# TurntableStrobe2.net
KiCad netlist of a schematic drawn in EAGLE
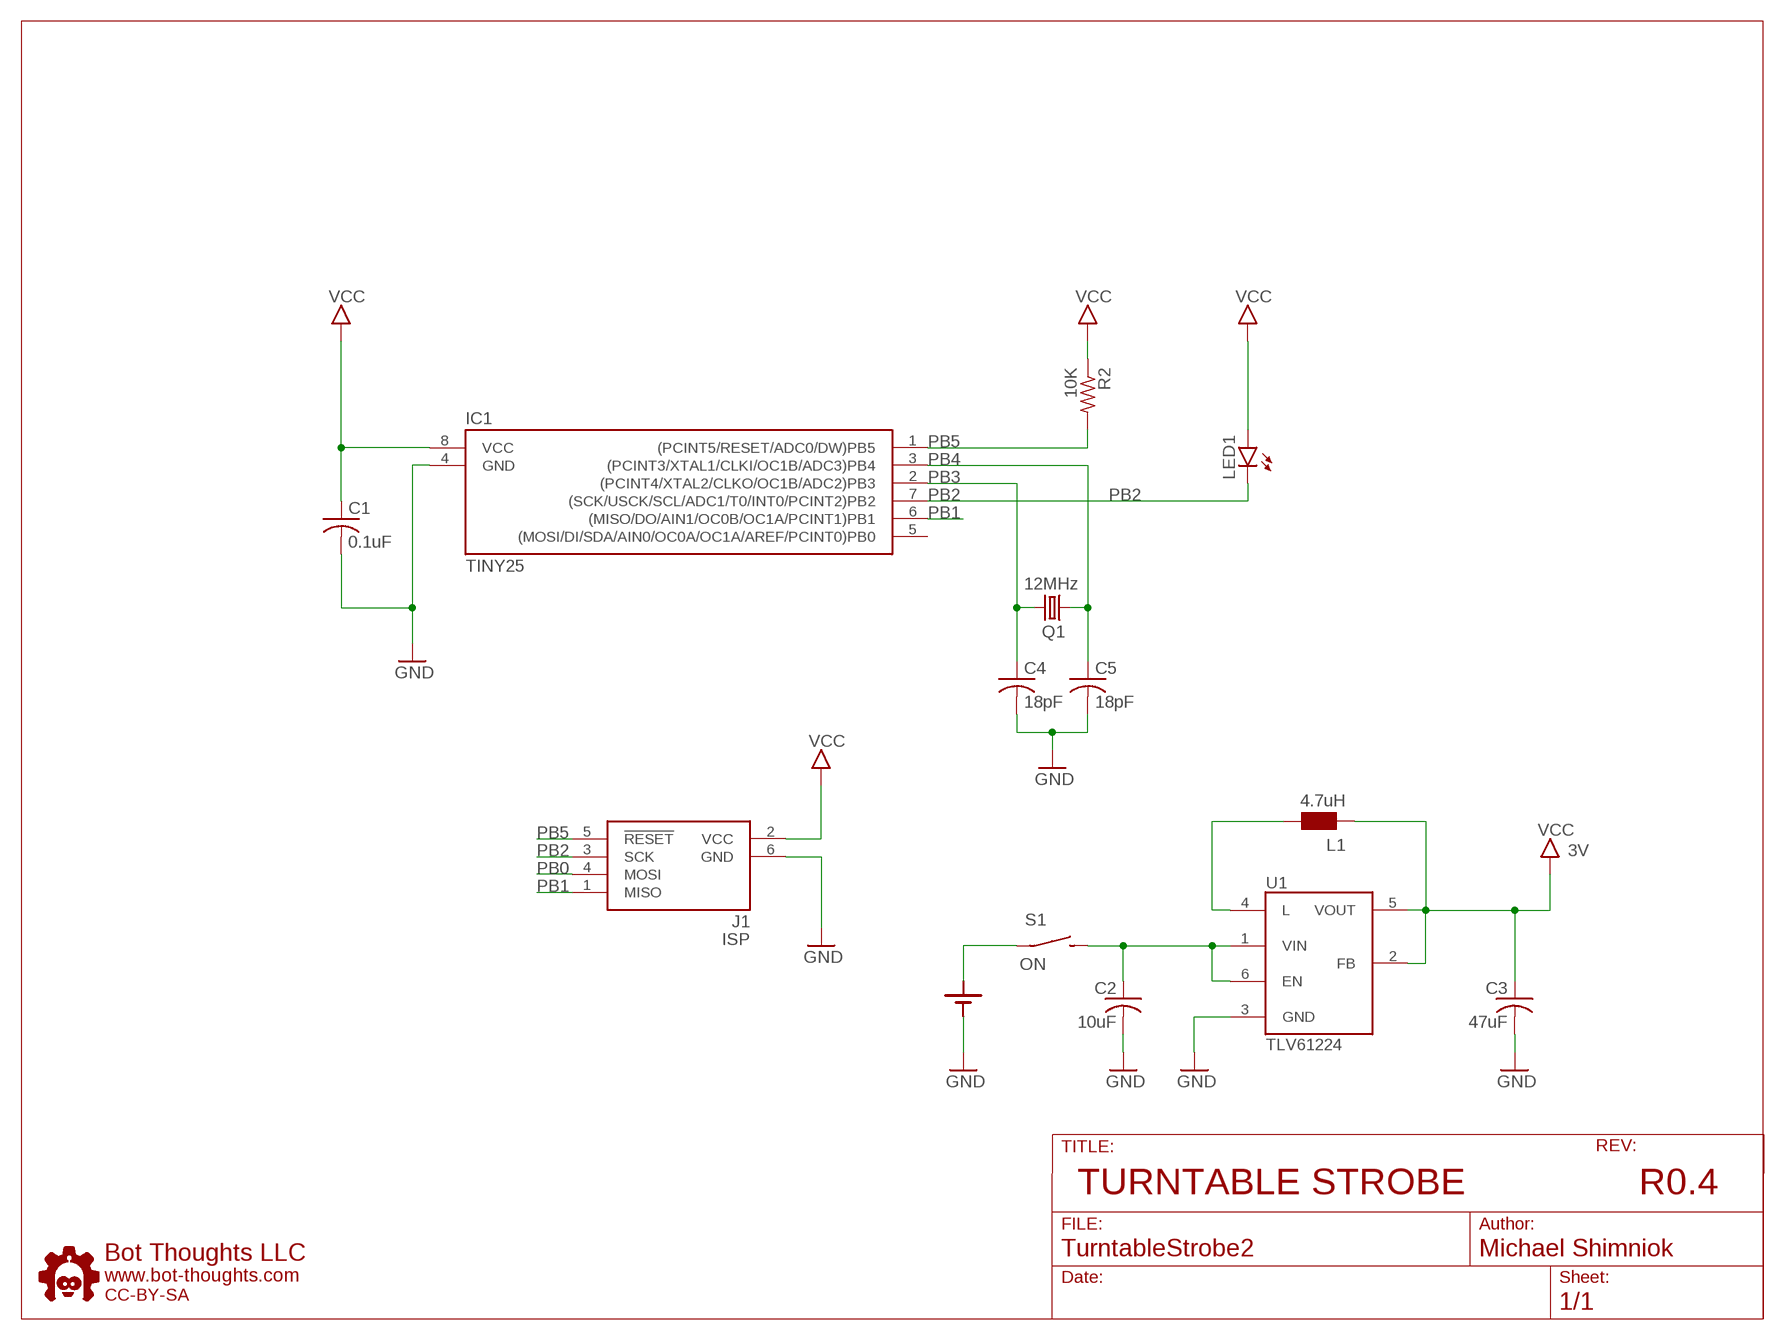
[diagram p0: schematic, sheet 1]

(export (version "E")
  (design (tool "Eeschema 10.0.6"))
  (components
    (comp (ref "C1")
      (value "0.1uF")
      (footprint "eagle-import:C0603")
      (libsource (lib "eagle-import") (part "C-USC0603"))
    )
    (comp (ref "C2")
      (value "10uF")
      (footprint "eagle-import:C0603")
      (libsource (lib "eagle-import") (part "C-USC0603"))
    )
    (comp (ref "C3")
      (value "47uF")
      (footprint "eagle-import:1206")
      (libsource (lib "eagle-import") (part "C-1206"))
    )
    (comp (ref "C4")
      (value "18pF")
      (footprint "eagle-import:C0603")
      (libsource (lib "eagle-import") (part "C-USC0603"))
    )
    (comp (ref "C5")
      (value "18pF")
      (footprint "eagle-import:C0603")
      (libsource (lib "eagle-import") (part "C-USC0603"))
    )
    (comp (ref "CR1225")
      (value "LR44_PTH")
      (footprint "eagle-import:LR44")
      (libsource (lib "eagle-import") (part "LR44_PTH"))
    )
    (comp (ref "IC1")
      (value "TINY25")
      (footprint "eagle-import:SOIC8N")
      (libsource (lib "eagle-import") (part "TINY25-20SSU"))
    )
    (comp (ref "J1")
      (value "ISP")
      (footprint "eagle-import:2X3_TP")
      (libsource (lib "eagle-import") (part "AVRISP6_TP"))
    )
    (comp (ref "L1")
      (value "4.7uH")
      (footprint "eagle-import:0805")
      (libsource (lib "eagle-import") (part "WE-MI_0805"))
    )
    (comp (ref "LED1")
      (value "LED5MMRA")
      (footprint "eagle-import:LED5MMRA")
      (libsource (lib "eagle-import") (part "LED5MMRA"))
    )
    (comp (ref "Q1")
      (value "12MHz")
      (footprint "eagle-import:NDK_2PAD_5X3")
      (libsource (lib "eagle-import") (part "CRYSTALNDK5X3"))
    )
    (comp (ref "R2")
      (value "10K")
      (footprint "eagle-import:R0603")
      (libsource (lib "eagle-import") (part "R-US_R0603"))
    )
    (comp (ref "S1")
      (value "ON")
      (footprint "eagle-import:6MMTACTILE_RECT")
      (libsource (lib "eagle-import") (part "SPST_TAC_RECT1"))
    )
    (comp (ref "U$5")
      (value "BTLOGO-LOGO-MD")
      (footprint "eagle-import:BTLOGOM")
      (libsource (lib "eagle-import") (part "BTLOGO-LOGO-MD"))
    )
    (comp (ref "U1")
      (value "TLV61224")
      (footprint "eagle-import:SC70-6")
      (libsource (lib "eagle-import") (part "TLV61224"))
    )
  )
  (nets
    (net (code "1") (name "/PB0") (class "Default")
      (node (ref "J1") (pin "4") (pinfunction "MOSI_4") (pintype "output"))
    )
    (net (code "2") (name "/PB1") (class "Default")
      (node (ref "IC1") (pin "6") (pinfunction "(MISO/DO/AIN1/OC0B/OC1A/PCINT1)PB1_6") (pintype "bidirectional"))
      (node (ref "J1") (pin "1") (pinfunction "MISO_1") (pintype "input"))
    )
    (net (code "3") (name "/PB2") (class "Default")
      (node (ref "IC1") (pin "7") (pinfunction "(SCK/USCK/SCL/ADC1/T0/INT0/PCINT2)PB2_7") (pintype "bidirectional"))
      (node (ref "J1") (pin "3") (pinfunction "SCK_3") (pintype "output"))
      (node (ref "LED1") (pin "C") (pinfunction "C_C") (pintype "passive"))
    )
    (net (code "4") (name "/PB3") (class "Default")
      (node (ref "C4") (pin "1") (pinfunction "1_1") (pintype "passive"))
      (node (ref "IC1") (pin "2") (pinfunction "(PCINT4/XTAL2/CLKO/OC1B/ADC2)PB3_2") (pintype "bidirectional"))
      (node (ref "Q1") (pin "P$2") (pinfunction "2_P$2") (pintype "passive"))
    )
    (net (code "5") (name "/PB4") (class "Default")
      (node (ref "C5") (pin "1") (pinfunction "1_1") (pintype "passive"))
      (node (ref "IC1") (pin "3") (pinfunction "(PCINT3/XTAL1/CLKI/OC1B/ADC3)PB4_3") (pintype "bidirectional"))
      (node (ref "Q1") (pin "P$1") (pinfunction "1_P$1") (pintype "passive"))
    )
    (net (code "6") (name "/PB5") (class "Default")
      (node (ref "IC1") (pin "1") (pinfunction "(PCINT5/RESET/ADC0/DW)PB5_1") (pintype "bidirectional"))
      (node (ref "J1") (pin "5") (pinfunction "~{RESET}_5") (pintype "output"))
      (node (ref "R2") (pin "2") (pinfunction "2_2") (pintype "passive"))
    )
    (net (code "7") (name "3V") (class "Default")
      (node (ref "C1") (pin "1") (pinfunction "1_1") (pintype "passive"))
      (node (ref "C3") (pin "1") (pinfunction "+_1") (pintype "passive"))
      (node (ref "IC1") (pin "8") (pinfunction "VCC_8") (pintype "power_in"))
      (node (ref "J1") (pin "2") (pinfunction "VCC_2") (pintype "power_in"))
      (node (ref "L1") (pin "1") (pinfunction "1_1") (pintype "passive"))
      (node (ref "LED1") (pin "A") (pinfunction "A_A") (pintype "passive"))
      (node (ref "R2") (pin "1") (pinfunction "1_1") (pintype "passive"))
      (node (ref "U1") (pin "2") (pinfunction "FB_2") (pintype "bidirectional"))
      (node (ref "U1") (pin "5") (pinfunction "VOUT_5") (pintype "bidirectional"))
    )
    (net (code "8") (name "GND") (class "Default")
      (node (ref "C1") (pin "2") (pinfunction "2_2") (pintype "passive"))
      (node (ref "C2") (pin "2") (pinfunction "2_2") (pintype "passive"))
      (node (ref "C3") (pin "2") (pinfunction "-_2") (pintype "passive"))
      (node (ref "C4") (pin "2") (pinfunction "2_2") (pintype "passive"))
      (node (ref "C5") (pin "2") (pinfunction "2_2") (pintype "passive"))
      (node (ref "CR1225") (pin "GND") (pinfunction "-_GND") (pintype "passive"))
      (node (ref "IC1") (pin "4") (pinfunction "GND_4") (pintype "power_in"))
      (node (ref "J1") (pin "6") (pinfunction "GND_6") (pintype "power_in"))
      (node (ref "U1") (pin "3") (pinfunction "GND_3") (pintype "bidirectional"))
    )
    (net (code "9") (name "Net-(S1-P)") (class "Default")
      (node (ref "CR1225") (pin "+1") (pinfunction "+_+1") (pintype "passive"))
      (node (ref "CR1225") (pin "+2") (pinfunction "+_+2") (pintype "passive"))
      (node (ref "S1") (pin "P$1") (pinfunction "P_P$1") (pintype "passive"))
    )
    (net (code "10") (name "Net-(S1-S)") (class "Default")
      (node (ref "C2") (pin "1") (pinfunction "1_1") (pintype "passive"))
      (node (ref "S1") (pin "P$2") (pinfunction "S_P$2") (pintype "passive"))
      (node (ref "U1") (pin "1") (pinfunction "VIN_1") (pintype "bidirectional"))
      (node (ref "U1") (pin "6") (pinfunction "EN_6") (pintype "bidirectional"))
    )
    (net (code "11") (name "Net-(U1-L)") (class "Default")
      (node (ref "L1") (pin "2") (pinfunction "2_2") (pintype "passive"))
      (node (ref "U1") (pin "4") (pinfunction "L_4") (pintype "bidirectional"))
    )
    (net (code "12") (name "unconnected-(IC1-(MOSI{slash}DI{slash}SDA{slash}AIN0{slash}OC0A{slash}OC1A{slash}AREF{slash}PCINT0)PB0-Pad5)") (class "Default")
      (node (ref "IC1") (pin "5") (pinfunction "(MOSI/DI/SDA/AIN0/OC0A/OC1A/AREF/PCINT0)PB0_5") (pintype "bidirectional"))
    )
  )
)
